# base.net
KiCad netlist of a schematic drawn in EAGLE
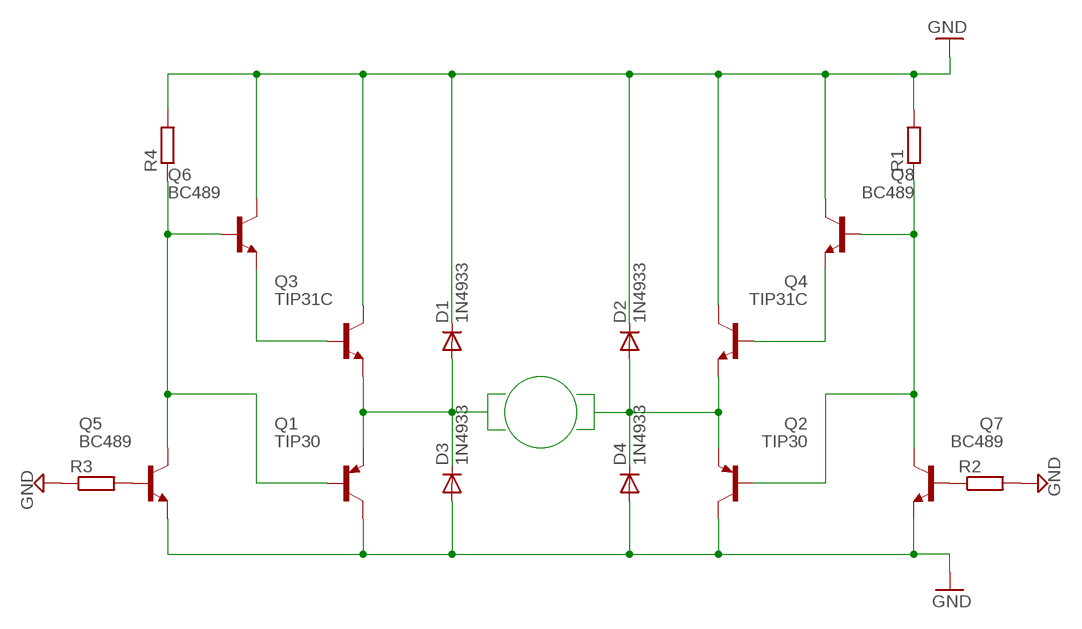
[diagram p0: schematic, sheet 1]

(export (version "E")
  (design (tool "Eeschema 10.0.6"))
  (components
    (comp (ref "D1")
      (value "1N4933")
      (footprint "eagle-import:DO41-10")
      (libsource (lib "eagle-import") (part "1N4933"))
    )
    (comp (ref "D2")
      (value "1N4933")
      (footprint "eagle-import:DO41-10")
      (libsource (lib "eagle-import") (part "1N4933"))
    )
    (comp (ref "D3")
      (value "1N4933")
      (footprint "eagle-import:DO41-10")
      (libsource (lib "eagle-import") (part "1N4933"))
    )
    (comp (ref "D4")
      (value "1N4933")
      (footprint "eagle-import:DO41-10")
      (libsource (lib "eagle-import") (part "1N4933"))
    )
    (comp (ref "Q1")
      (value "TIP30")
      (footprint "eagle-import:TO220")
      (libsource (lib "eagle-import") (part "TIP30"))
    )
    (comp (ref "Q2")
      (value "TIP30")
      (footprint "eagle-import:TO220")
      (libsource (lib "eagle-import") (part "TIP30"))
    )
    (comp (ref "Q3")
      (value "TIP31C")
      (footprint "eagle-import:TO220")
      (libsource (lib "eagle-import") (part "TIP31C"))
    )
    (comp (ref "Q4")
      (value "TIP31C")
      (footprint "eagle-import:TO220")
      (libsource (lib "eagle-import") (part "TIP31C"))
    )
    (comp (ref "Q5")
      (value "BC489")
      (footprint "eagle-import:TO92-EBC")
      (libsource (lib "eagle-import") (part "BC489"))
    )
    (comp (ref "Q6")
      (value "BC489")
      (footprint "eagle-import:TO92-EBC")
      (libsource (lib "eagle-import") (part "BC489"))
    )
    (comp (ref "Q7")
      (value "BC489")
      (footprint "eagle-import:TO92-EBC")
      (libsource (lib "eagle-import") (part "BC489"))
    )
    (comp (ref "Q8")
      (value "BC489")
      (footprint "eagle-import:TO92-EBC")
      (libsource (lib "eagle-import") (part "BC489"))
    )
    (comp (ref "R1")
      (value "R-EU_0204/7")
      (footprint "eagle-import:0204_7")
      (libsource (lib "eagle-import") (part "R-EU_0204/7"))
    )
    (comp (ref "R2")
      (value "R-EU_0204/7")
      (footprint "eagle-import:0204_7")
      (libsource (lib "eagle-import") (part "R-EU_0204/7"))
    )
    (comp (ref "R3")
      (value "R-EU_0204/7")
      (footprint "eagle-import:0204_7")
      (libsource (lib "eagle-import") (part "R-EU_0204/7"))
    )
    (comp (ref "R4")
      (value "R-EU_0204/7")
      (footprint "eagle-import:0204_7")
      (libsource (lib "eagle-import") (part "R-EU_0204/7"))
    )
  )
  (nets
    (net (code "1") (name "GND") (class "Default")
      (node (ref "D1") (pin "C") (pinfunction "C_C") (pintype "passive"))
      (node (ref "D2") (pin "C") (pinfunction "C_C") (pintype "passive"))
      (node (ref "D3") (pin "A") (pinfunction "A_A") (pintype "passive"))
      (node (ref "D4") (pin "A") (pinfunction "A_A") (pintype "passive"))
      (node (ref "Q1") (pin "2") (pinfunction "C_2") (pintype "passive"))
      (node (ref "Q2") (pin "2") (pinfunction "C_2") (pintype "passive"))
      (node (ref "Q3") (pin "2") (pinfunction "C_2") (pintype "passive"))
      (node (ref "Q4") (pin "2") (pinfunction "C_2") (pintype "passive"))
      (node (ref "Q5") (pin "E") (pinfunction "E_E") (pintype "passive"))
      (node (ref "Q6") (pin "C") (pinfunction "C_C") (pintype "passive"))
      (node (ref "Q7") (pin "E") (pinfunction "E_E") (pintype "passive"))
      (node (ref "Q8") (pin "C") (pinfunction "C_C") (pintype "passive"))
      (node (ref "R1") (pin "2") (pinfunction "2_2") (pintype "passive"))
      (node (ref "R2") (pin "2") (pinfunction "2_2") (pintype "passive"))
      (node (ref "R3") (pin "1") (pinfunction "1_1") (pintype "passive"))
      (node (ref "R4") (pin "2") (pinfunction "2_2") (pintype "passive"))
    )
    (net (code "2") (name "Net-(Q1-B)") (class "Default")
      (node (ref "Q1") (pin "1") (pinfunction "B_1") (pintype "passive"))
      (node (ref "Q5") (pin "C") (pinfunction "C_C") (pintype "passive"))
      (node (ref "Q6") (pin "B") (pinfunction "B_B") (pintype "passive"))
      (node (ref "R4") (pin "1") (pinfunction "1_1") (pintype "passive"))
    )
    (net (code "3") (name "Net-(Q1-E)") (class "Default")
      (node (ref "D1") (pin "A") (pinfunction "A_A") (pintype "passive"))
      (node (ref "D3") (pin "C") (pinfunction "C_C") (pintype "passive"))
      (node (ref "Q1") (pin "3") (pinfunction "E_3") (pintype "passive"))
      (node (ref "Q3") (pin "3") (pinfunction "E_3") (pintype "passive"))
    )
    (net (code "4") (name "Net-(Q2-B)") (class "Default")
      (node (ref "Q2") (pin "1") (pinfunction "B_1") (pintype "passive"))
      (node (ref "Q7") (pin "C") (pinfunction "C_C") (pintype "passive"))
      (node (ref "Q8") (pin "B") (pinfunction "B_B") (pintype "passive"))
      (node (ref "R1") (pin "1") (pinfunction "1_1") (pintype "passive"))
    )
    (net (code "5") (name "Net-(Q2-E)") (class "Default")
      (node (ref "D2") (pin "A") (pinfunction "A_A") (pintype "passive"))
      (node (ref "D4") (pin "C") (pinfunction "C_C") (pintype "passive"))
      (node (ref "Q2") (pin "3") (pinfunction "E_3") (pintype "passive"))
      (node (ref "Q4") (pin "3") (pinfunction "E_3") (pintype "passive"))
    )
    (net (code "6") (name "Net-(Q3-B)") (class "Default")
      (node (ref "Q3") (pin "1") (pinfunction "B_1") (pintype "passive"))
      (node (ref "Q6") (pin "E") (pinfunction "E_E") (pintype "passive"))
    )
    (net (code "7") (name "Net-(Q4-B)") (class "Default")
      (node (ref "Q4") (pin "1") (pinfunction "B_1") (pintype "passive"))
      (node (ref "Q8") (pin "E") (pinfunction "E_E") (pintype "passive"))
    )
    (net (code "8") (name "Net-(Q5-PadB)") (class "Default")
      (node (ref "Q5") (pin "B") (pinfunction "B_B") (pintype "passive"))
      (node (ref "R3") (pin "2") (pinfunction "2_2") (pintype "passive"))
    )
    (net (code "9") (name "Net-(Q7-PadB)") (class "Default")
      (node (ref "Q7") (pin "B") (pinfunction "B_B") (pintype "passive"))
      (node (ref "R2") (pin "1") (pinfunction "1_1") (pintype "passive"))
    )
  )
)
